# drive.net
KiCad netlist of a schematic drawn in Altium Designer
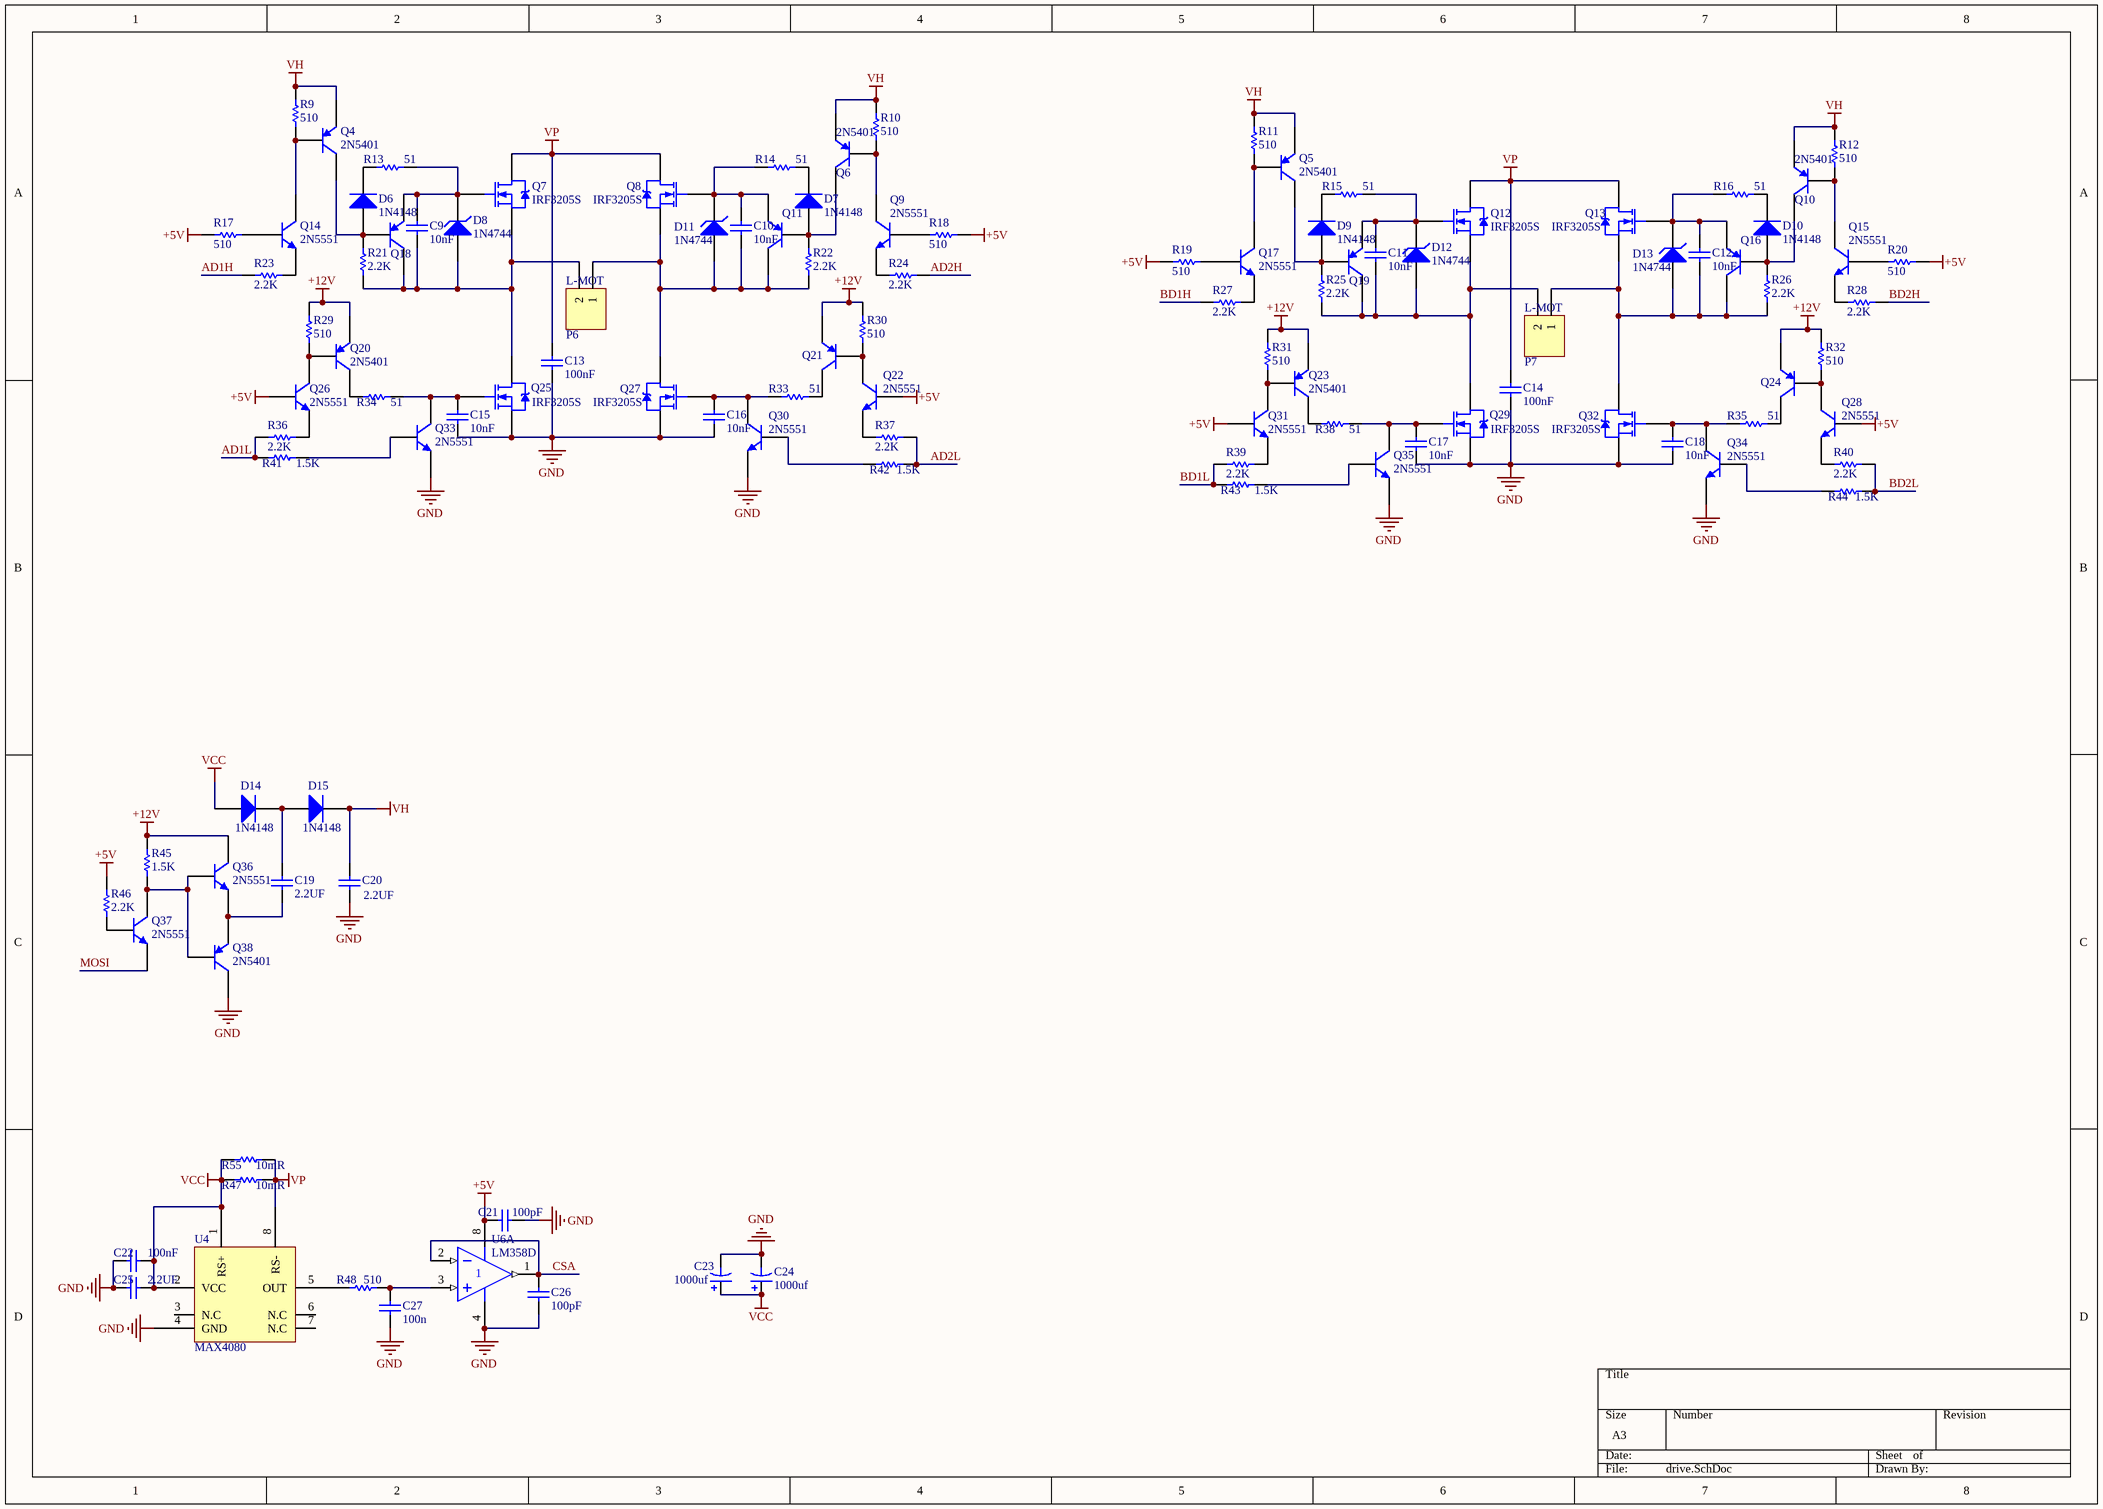
[diagram p0: drive.SchDoc]

(export (version "E")
  (design (tool "Eeschema 10.0.6"))
  (components
    (comp (ref "C9")
      (value "10nF")
      (footprint "0603")
      (description "Capacitor")
      (fields (field (name "Comment") "Cap") (field (name "PUBLISHER") "Altium Limited"))
      (libsource (lib "Miscellaneous Devices") (part "Cap"))
    )
    (comp (ref "C10")
      (value "10nF")
      (footprint "0603")
      (description "Capacitor")
      (fields (field (name "Comment") "Cap") (field (name "PUBLISHER") "Altium Limited"))
      (libsource (lib "Miscellaneous Devices") (part "Cap"))
    )
    (comp (ref "C11")
      (value "10nF")
      (footprint "0603")
      (description "Capacitor")
      (fields (field (name "Comment") "Cap") (field (name "PUBLISHER") "Altium Limited"))
      (libsource (lib "Miscellaneous Devices") (part "Cap"))
    )
    (comp (ref "C12")
      (value "10nF")
      (footprint "0603")
      (description "Capacitor")
      (fields (field (name "Comment") "Cap") (field (name "PUBLISHER") "Altium Limited"))
      (libsource (lib "Miscellaneous Devices") (part "Cap"))
    )
    (comp (ref "C13")
      (value "100nF")
      (footprint "3216[1206]")
      (description "Capacitor")
      (fields (field (name "Comment") "Cap") (field (name "PUBLISHER") "Altium Limited"))
      (libsource (lib "Miscellaneous Devices") (part "Cap"))
    )
    (comp (ref "C14")
      (value "100nF")
      (footprint "3216[1206]")
      (description "Capacitor")
      (fields (field (name "Comment") "Cap") (field (name "PUBLISHER") "Altium Limited"))
      (libsource (lib "Miscellaneous Devices") (part "Cap"))
    )
    (comp (ref "C15")
      (value "10nF")
      (footprint "0603")
      (description "Capacitor")
      (fields (field (name "Comment") "Cap") (field (name "PUBLISHER") "Altium Limited"))
      (libsource (lib "Miscellaneous Devices") (part "Cap"))
    )
    (comp (ref "C16")
      (value "10nF")
      (footprint "0603")
      (description "Capacitor")
      (fields (field (name "Comment") "Cap") (field (name "PUBLISHER") "Altium Limited"))
      (libsource (lib "Miscellaneous Devices") (part "Cap"))
    )
    (comp (ref "C17")
      (value "10nF")
      (footprint "0603")
      (description "Capacitor")
      (fields (field (name "Comment") "Cap") (field (name "PUBLISHER") "Altium Limited"))
      (libsource (lib "Miscellaneous Devices") (part "Cap"))
    )
    (comp (ref "C18")
      (value "10nF")
      (footprint "0603")
      (description "Capacitor")
      (fields (field (name "Comment") "Cap") (field (name "PUBLISHER") "Altium Limited"))
      (libsource (lib "Miscellaneous Devices") (part "Cap"))
    )
    (comp (ref "C19")
      (value "2.2UF")
      (footprint "C1206")
      (description "Capacitor")
      (fields (field (name "Comment") "Cap") (field (name "PUBLISHER") "Altium Limited"))
      (libsource (lib "Miscellaneous Devices") (part "Cap"))
    )
    (comp (ref "C20")
      (value "2.2UF")
      (footprint "C1206")
      (description "Capacitor")
      (fields (field (name "Comment") "Cap") (field (name "PUBLISHER") "Altium Limited"))
      (libsource (lib "Miscellaneous Devices") (part "Cap"))
    )
    (comp (ref "C21")
      (value "100pF")
      (footprint "0603")
      (description "Capacitor")
      (fields (field (name "Comment") "Cap") (field (name "PUBLISHER") "Altium Limited"))
      (libsource (lib "Miscellaneous Devices") (part "Cap"))
    )
    (comp (ref "C22")
      (value "100nF")
      (footprint "0603")
      (description "Capacitor")
      (fields (field (name "Comment") "Cap") (field (name "PUBLISHER") "Altium Limited"))
      (libsource (lib "Miscellaneous Devices") (part "Cap"))
    )
    (comp (ref "C23")
      (value "1000uf")
      (footprint "C16-7.5")
      (description "Polarized Capacitor (Radial)")
      (fields (field (name "Comment") "Cap Pol1") (field (name "PUBLISHER") "Altium Limited"))
      (libsource (lib "Miscellaneous Devices") (part "Cap Pol1"))
    )
    (comp (ref "C24")
      (value "1000uf")
      (footprint "C16-7.5")
      (description "Polarized Capacitor (Radial)")
      (fields (field (name "Comment") "Cap Pol1") (field (name "PUBLISHER") "Altium Limited"))
      (libsource (lib "Miscellaneous Devices") (part "Cap Pol1"))
    )
    (comp (ref "C25")
      (value "2.2UF")
      (footprint "3216[1206]")
      (description "Capacitor")
      (fields (field (name "Comment") "Cap") (field (name "PUBLISHER") "Altium Limited"))
      (libsource (lib "Miscellaneous Devices") (part "Cap"))
    )
    (comp (ref "C26")
      (value "100pF")
      (footprint "0603")
      (description "Capacitor")
      (fields (field (name "Comment") "Cap") (field (name "PUBLISHER") "Altium Limited"))
      (libsource (lib "Miscellaneous Devices") (part "Cap"))
    )
    (comp (ref "C27")
      (value "100n")
      (footprint "0603")
      (description "Capacitor")
      (fields (field (name "Comment") "Cap") (field (name "PUBLISHER") "Altium Limited"))
      (libsource (lib "Miscellaneous Devices") (part "Cap"))
    )
    (comp (ref "D6")
      (value "1N4148")
      (footprint "LL34")
      (description "High Conductance Fast Diode")
      (fields (field (name "PUBLISHER") "Altium Limited"))
      (libsource (lib "Miscellaneous Devices") (part "Diode 1N4148"))
    )
    (comp (ref "D7")
      (value "1N4148")
      (footprint "LL34")
      (description "High Conductance Fast Diode")
      (fields (field (name "PUBLISHER") "Altium Limited"))
      (libsource (lib "Miscellaneous Devices") (part "Diode 1N4148"))
    )
    (comp (ref "D8")
      (value "1N4744")
      (footprint "LL34")
      (description "Zener Diode")
      (fields (field (name "PUBLISHER") "Altium Limited"))
      (libsource (lib "Miscellaneous Devices") (part "D Zener"))
    )
    (comp (ref "D9")
      (value "1N4148")
      (footprint "LL34")
      (description "High Conductance Fast Diode")
      (fields (field (name "PUBLISHER") "Altium Limited"))
      (libsource (lib "Miscellaneous Devices") (part "Diode 1N4148"))
    )
    (comp (ref "D10")
      (value "1N4148")
      (footprint "LL34")
      (description "High Conductance Fast Diode")
      (fields (field (name "PUBLISHER") "Altium Limited"))
      (libsource (lib "Miscellaneous Devices") (part "Diode 1N4148"))
    )
    (comp (ref "D11")
      (value "1N4744")
      (footprint "LL34")
      (description "Zener Diode")
      (fields (field (name "PUBLISHER") "Altium Limited"))
      (libsource (lib "Miscellaneous Devices") (part "D Zener"))
    )
    (comp (ref "D12")
      (value "1N4744")
      (footprint "LL34")
      (description "Zener Diode")
      (fields (field (name "PUBLISHER") "Altium Limited"))
      (libsource (lib "Miscellaneous Devices") (part "D Zener"))
    )
    (comp (ref "D13")
      (value "1N4744")
      (footprint "LL34")
      (description "Zener Diode")
      (fields (field (name "PUBLISHER") "Altium Limited"))
      (libsource (lib "Miscellaneous Devices") (part "D Zener"))
    )
    (comp (ref "D14")
      (value "1N4148")
      (footprint "LL34")
      (description "3 Amp Medium Power Silicon Rectifier Diode")
      (fields (field (name "Comment") "Diode") (field (name "PUBLISHER") "Altium Limited"))
      (libsource (lib "Miscellaneous Devices") (part "Diode 1N5408"))
    )
    (comp (ref "D15")
      (value "1N4148")
      (footprint "LL34")
      (description "3 Amp Medium Power Silicon Rectifier Diode")
      (fields (field (name "Comment") "Diode") (field (name "PUBLISHER") "Altium Limited"))
      (libsource (lib "Miscellaneous Devices") (part "Diode 1N5408"))
    )
    (comp (ref "P6")
      (value "L-MOT")
      (footprint "MG7.62-2P")
      (description "Header, 2-Pin")
      (fields (field (name "PUBLISHER") "Altium Limited"))
      (libsource (lib "Miscellaneous Connectors") (part "Header 2"))
    )
    (comp (ref "P7")
      (value "L-MOT")
      (footprint "MG7.62-2P")
      (description "Header, 2-Pin")
      (fields (field (name "PUBLISHER") "Altium Limited"))
      (libsource (lib "Miscellaneous Connectors") (part "Header 2"))
    )
    (comp (ref "Q4")
      (value "2N5401")
      (footprint "SOT-23-PNP")
      (description "PNP General Purpose Amplifier")
      (fields (field (name "PUBLISHER") "Altium Limited"))
      (libsource (lib "FSC Discrete BJT") (part "2N5401"))
    )
    (comp (ref "Q5")
      (value "2N5401")
      (footprint "SOT-23-PNP")
      (description "PNP General Purpose Amplifier")
      (fields (field (name "PUBLISHER") "Altium Limited"))
      (libsource (lib "FSC Discrete BJT") (part "2N5401"))
    )
    (comp (ref "Q6")
      (value "2N5401")
      (footprint "SOT-23-PNP")
      (description "PNP General Purpose Amplifier")
      (fields (field (name "PUBLISHER") "Altium Limited"))
      (libsource (lib "FSC Discrete BJT") (part "2N5401"))
    )
    (comp (ref "Q7")
      (value "IRF3205S")
      (footprint "D2PAK-263")
      (description "HEXFET Power MOSFET")
      (fields (field (name "PUBLISHER") "Altium Limited"))
      (libsource (lib "Tank") (part "IRF3205S"))
    )
    (comp (ref "Q8")
      (value "IRF3205S")
      (footprint "D2PAK-263")
      (description "HEXFET Power MOSFET")
      (fields (field (name "PUBLISHER") "Altium Limited"))
      (libsource (lib "IR Discrete MOSFET - Power") (part "IRF3205S"))
    )
    (comp (ref "Q9")
      (value "2N5551")
      (footprint "SOT-23-NPN")
      (description "NPN General Purpose Amplifier")
      (fields (field (name "PUBLISHER") "Altium Limited"))
      (libsource (lib "FSC Discrete BJT") (part "2N5551"))
    )
    (comp (ref "Q10")
      (value "2N5401")
      (footprint "SOT-23-PNP")
      (description "PNP General Purpose Amplifier")
      (fields (field (name "PUBLISHER") "Altium Limited"))
      (libsource (lib "FSC Discrete BJT") (part "2N5401"))
    )
    (comp (ref "Q11")
      (value "2N5401")
      (footprint "SOT-23-PNP")
      (description "PNP General Purpose Amplifier")
      (fields (field (name "PUBLISHER") "Altium Limited"))
      (libsource (lib "FSC Discrete BJT") (part "2N5401"))
    )
    (comp (ref "Q12")
      (value "IRF3205S")
      (footprint "D2PAK-263")
      (description "HEXFET Power MOSFET")
      (fields (field (name "PUBLISHER") "Altium Limited"))
      (libsource (lib "Tank") (part "IRF3205S"))
    )
    (comp (ref "Q13")
      (value "IRF3205S")
      (footprint "D2PAK-263")
      (description "HEXFET Power MOSFET")
      (fields (field (name "PUBLISHER") "Altium Limited"))
      (libsource (lib "IR Discrete MOSFET - Power") (part "IRF3205S"))
    )
    (comp (ref "Q14")
      (value "2N5551")
      (footprint "SOT-23-NPN")
      (description "NPN General Purpose Amplifier")
      (fields (field (name "PUBLISHER") "Altium Limited"))
      (libsource (lib "FSC Discrete BJT") (part "2N5551"))
    )
    (comp (ref "Q15")
      (value "2N5551")
      (footprint "SOT-23-NPN")
      (description "NPN General Purpose Amplifier")
      (fields (field (name "PUBLISHER") "Altium Limited"))
      (libsource (lib "FSC Discrete BJT") (part "2N5551"))
    )
    (comp (ref "Q16")
      (value "2N5401")
      (footprint "SOT-23-PNP")
      (description "PNP General Purpose Amplifier")
      (fields (field (name "PUBLISHER") "Altium Limited"))
      (libsource (lib "FSC Discrete BJT") (part "2N5401"))
    )
    (comp (ref "Q17")
      (value "2N5551")
      (footprint "SOT-23-NPN")
      (description "NPN General Purpose Amplifier")
      (fields (field (name "PUBLISHER") "Altium Limited"))
      (libsource (lib "FSC Discrete BJT") (part "2N5551"))
    )
    (comp (ref "Q18")
      (value "2N5401")
      (footprint "SOT-23-PNP")
      (description "PNP General Purpose Amplifier")
      (fields (field (name "PUBLISHER") "Altium Limited"))
      (libsource (lib "FSC Discrete BJT") (part "2N5401"))
    )
    (comp (ref "Q19")
      (value "2N5401")
      (footprint "SOT-23-PNP")
      (description "PNP General Purpose Amplifier")
      (fields (field (name "PUBLISHER") "Altium Limited"))
      (libsource (lib "FSC Discrete BJT") (part "2N5401"))
    )
    (comp (ref "Q20")
      (value "2N5401")
      (footprint "SOT-23-PNP")
      (description "PNP General Purpose Amplifier")
      (fields (field (name "PUBLISHER") "Altium Limited"))
      (libsource (lib "FSC Discrete BJT") (part "2N5401"))
    )
    (comp (ref "Q21")
      (value "2N5401")
      (footprint "SOT-23-PNP")
      (description "PNP General Purpose Amplifier")
      (fields (field (name "PUBLISHER") "Altium Limited"))
      (libsource (lib "FSC Discrete BJT") (part "2N5401"))
    )
    (comp (ref "Q22")
      (value "2N5551")
      (footprint "SOT-23-NPN")
      (description "NPN General Purpose Amplifier")
      (fields (field (name "PUBLISHER") "Altium Limited"))
      (libsource (lib "FSC Discrete BJT") (part "2N5551"))
    )
    (comp (ref "Q23")
      (value "2N5401")
      (footprint "SOT-23-PNP")
      (description "PNP General Purpose Amplifier")
      (fields (field (name "PUBLISHER") "Altium Limited"))
      (libsource (lib "FSC Discrete BJT") (part "2N5401"))
    )
    (comp (ref "Q24")
      (value "2N5401")
      (footprint "SOT-23-PNP")
      (description "PNP General Purpose Amplifier")
      (fields (field (name "PUBLISHER") "Altium Limited"))
      (libsource (lib "FSC Discrete BJT") (part "2N5401"))
    )
    (comp (ref "Q25")
      (value "IRF3205S")
      (footprint "D2PAK-263")
      (description "HEXFET Power MOSFET")
      (fields (field (name "PUBLISHER") "Altium Limited"))
      (libsource (lib "IR Discrete MOSFET - Power") (part "IRF3205S"))
    )
    (comp (ref "Q26")
      (value "2N5551")
      (footprint "SOT-23-NPN")
      (description "NPN General Purpose Amplifier")
      (fields (field (name "PUBLISHER") "Altium Limited"))
      (libsource (lib "FSC Discrete BJT") (part "2N5551"))
    )
    (comp (ref "Q27")
      (value "IRF3205S")
      (footprint "D2PAK-263")
      (description "HEXFET Power MOSFET")
      (fields (field (name "PUBLISHER") "Altium Limited"))
      (libsource (lib "IR Discrete MOSFET - Power") (part "IRF3205S"))
    )
    (comp (ref "Q28")
      (value "2N5551")
      (footprint "SOT-23-NPN")
      (description "NPN General Purpose Amplifier")
      (fields (field (name "PUBLISHER") "Altium Limited"))
      (libsource (lib "FSC Discrete BJT") (part "2N5551"))
    )
    (comp (ref "Q29")
      (value "IRF3205S")
      (footprint "D2PAK-263")
      (description "HEXFET Power MOSFET")
      (fields (field (name "PUBLISHER") "Altium Limited"))
      (libsource (lib "IR Discrete MOSFET - Power") (part "IRF3205S"))
    )
    (comp (ref "Q30")
      (value "2N5551")
      (footprint "SOT-23-NPN")
      (description "NPN General Purpose Amplifier")
      (fields (field (name "PUBLISHER") "Altium Limited"))
      (libsource (lib "FSC Discrete BJT") (part "2N5551"))
    )
    (comp (ref "Q31")
      (value "2N5551")
      (footprint "SOT-23-NPN")
      (description "NPN General Purpose Amplifier")
      (fields (field (name "PUBLISHER") "Altium Limited"))
      (libsource (lib "FSC Discrete BJT") (part "2N5551"))
    )
    (comp (ref "Q32")
      (value "IRF3205S")
      (footprint "D2PAK-263")
      (description "HEXFET Power MOSFET")
      (fields (field (name "PUBLISHER") "Altium Limited"))
      (libsource (lib "IR Discrete MOSFET - Power") (part "IRF3205S"))
    )
    (comp (ref "Q33")
      (value "2N5551")
      (footprint "SOT-23-NPN")
      (description "NPN General Purpose Amplifier")
      (fields (field (name "PUBLISHER") "Altium Limited"))
      (libsource (lib "FSC Discrete BJT") (part "2N5551"))
    )
    (comp (ref "Q34")
      (value "2N5551")
      (footprint "SOT-23-NPN")
      (description "NPN General Purpose Amplifier")
      (fields (field (name "PUBLISHER") "Altium Limited"))
      (libsource (lib "FSC Discrete BJT") (part "2N5551"))
    )
    (comp (ref "Q35")
      (value "2N5551")
      (footprint "SOT-23-NPN")
      (description "NPN General Purpose Amplifier")
      (fields (field (name "PUBLISHER") "Altium Limited"))
      (libsource (lib "FSC Discrete BJT") (part "2N5551"))
    )
    (comp (ref "Q36")
      (value "2N5551")
      (footprint "SOT-23-NPN")
      (description "NPN General Purpose Amplifier")
      (fields (field (name "Comment") "NPN") (field (name "PUBLISHER") "Altium Limited"))
      (libsource (lib "FSC Discrete BJT") (part "2N5551"))
    )
    (comp (ref "Q37")
      (value "2N5551")
      (footprint "SOT-23-NPN")
      (description "NPN General Purpose Amplifier")
      (fields (field (name "Comment") "NPN") (field (name "PUBLISHER") "Altium Limited"))
      (libsource (lib "FSC Discrete BJT") (part "2N5551"))
    )
    (comp (ref "Q38")
      (value "2N5401")
      (footprint "SOT-23-PNP")
      (description "PNP General Purpose Amplifier")
      (fields (field (name "Comment") "PNP") (field (name "PUBLISHER") "Altium Limited"))
      (libsource (lib "FSC Discrete BJT") (part "2N5401"))
    )
    (comp (ref "R9")
      (value "510")
      (footprint "0603")
      (description "Resistor")
      (fields (field (name "Comment") "Res1") (field (name "PUBLISHER") "Altium Limited"))
      (libsource (lib "Miscellaneous Devices") (part "Res1"))
    )
    (comp (ref "R10")
      (value "510")
      (footprint "0603")
      (description "Resistor")
      (fields (field (name "Comment") "Res1") (field (name "PUBLISHER") "Altium Limited"))
      (libsource (lib "Miscellaneous Devices") (part "Res1"))
    )
    (comp (ref "R11")
      (value "510")
      (footprint "0603")
      (description "Resistor")
      (fields (field (name "Comment") "Res1") (field (name "PUBLISHER") "Altium Limited"))
      (libsource (lib "Miscellaneous Devices") (part "Res1"))
    )
    (comp (ref "R12")
      (value "510")
      (footprint "0603")
      (description "Resistor")
      (fields (field (name "Comment") "Res1") (field (name "PUBLISHER") "Altium Limited"))
      (libsource (lib "Miscellaneous Devices") (part "Res1"))
    )
    (comp (ref "R13")
      (value "51")
      (footprint "0603")
      (description "Resistor")
      (fields (field (name "Comment") "Res1") (field (name "PUBLISHER") "Altium Limited"))
      (libsource (lib "Miscellaneous Devices") (part "Res1"))
    )
    (comp (ref "R14")
      (value "51")
      (footprint "0603")
      (description "Resistor")
      (fields (field (name "Comment") "Res1") (field (name "PUBLISHER") "Altium Limited"))
      (libsource (lib "Miscellaneous Devices") (part "Res1"))
    )
    (comp (ref "R15")
      (value "51")
      (footprint "0603")
      (description "Resistor")
      (fields (field (name "Comment") "Res1") (field (name "PUBLISHER") "Altium Limited"))
      (libsource (lib "Miscellaneous Devices") (part "Res1"))
    )
    (comp (ref "R16")
      (value "51")
      (footprint "0603")
      (description "Resistor")
      (fields (field (name "Comment") "Res1") (field (name "PUBLISHER") "Altium Limited"))
      (libsource (lib "Miscellaneous Devices") (part "Res1"))
    )
    (comp (ref "R17")
      (value "510")
      (footprint "0603")
      (description "Resistor")
      (fields (field (name "Comment") "Res1") (field (name "PUBLISHER") "Altium Limited"))
      (libsource (lib "Miscellaneous Devices") (part "Res1"))
    )
    (comp (ref "R18")
      (value "510")
      (footprint "0603")
      (description "Resistor")
      (fields (field (name "Comment") "Res1") (field (name "PUBLISHER") "Altium Limited"))
      (libsource (lib "Miscellaneous Devices") (part "Res1"))
    )
    (comp (ref "R19")
      (value "510")
      (footprint "0603")
      (description "Resistor")
      (fields (field (name "Comment") "Res1") (field (name "PUBLISHER") "Altium Limited"))
      (libsource (lib "Miscellaneous Devices") (part "Res1"))
    )
    (comp (ref "R20")
      (value "510")
      (footprint "0603")
      (description "Resistor")
      (fields (field (name "Comment") "Res1") (field (name "PUBLISHER") "Altium Limited"))
      (libsource (lib "Miscellaneous Devices") (part "Res1"))
    )
    (comp (ref "R21")
      (value "2.2K")
      (footprint "0603")
      (description "Resistor")
      (fields (field (name "Comment") "Res1") (field (name "PUBLISHER") "Altium Limited"))
      (libsource (lib "Miscellaneous Devices") (part "Res1"))
    )
    (comp (ref "R22")
      (value "2.2K")
      (footprint "0603")
      (description "Resistor")
      (fields (field (name "Comment") "Res1") (field (name "PUBLISHER") "Altium Limited"))
      (libsource (lib "Miscellaneous Devices") (part "Res1"))
    )
    (comp (ref "R23")
      (value "2.2K")
      (footprint "0603")
      (description "Resistor")
      (fields (field (name "Comment") "Res1") (field (name "PUBLISHER") "Altium Limited"))
      (libsource (lib "Miscellaneous Devices") (part "Res1"))
    )
    (comp (ref "R24")
      (value "2.2K")
      (footprint "0603")
      (description "Resistor")
      (fields (field (name "Comment") "Res1") (field (name "PUBLISHER") "Altium Limited"))
      (libsource (lib "Miscellaneous Devices") (part "Res1"))
    )
    (comp (ref "R25")
      (value "2.2K")
      (footprint "0603")
      (description "Resistor")
      (fields (field (name "Comment") "Res1") (field (name "PUBLISHER") "Altium Limited"))
      (libsource (lib "Miscellaneous Devices") (part "Res1"))
    )
    (comp (ref "R26")
      (value "2.2K")
      (footprint "0603")
      (description "Resistor")
      (fields (field (name "Comment") "Res1") (field (name "PUBLISHER") "Altium Limited"))
      (libsource (lib "Miscellaneous Devices") (part "Res1"))
    )
    (comp (ref "R27")
      (value "2.2K")
      (footprint "0603")
      (description "Resistor")
      (fields (field (name "Comment") "Res1") (field (name "PUBLISHER") "Altium Limited"))
      (libsource (lib "Miscellaneous Devices") (part "Res1"))
    )
    (comp (ref "R28")
      (value "2.2K")
      (footprint "0603")
      (description "Resistor")
      (fields (field (name "Comment") "Res1") (field (name "PUBLISHER") "Altium Limited"))
      (libsource (lib "Miscellaneous Devices") (part "Res1"))
    )
    (comp (ref "R29")
      (value "510")
      (footprint "0603")
      (description "Resistor")
      (fields (field (name "Comment") "Res1") (field (name "PUBLISHER") "Altium Limited"))
      (libsource (lib "Miscellaneous Devices") (part "Res1"))
    )
    (comp (ref "R30")
      (value "510")
      (footprint "0603")
      (description "Resistor")
      (fields (field (name "Comment") "Res1") (field (name "PUBLISHER") "Altium Limited"))
      (libsource (lib "Miscellaneous Devices") (part "Res1"))
    )
    (comp (ref "R31")
      (value "510")
      (footprint "0603")
      (description "Resistor")
      (fields (field (name "Comment") "Res1") (field (name "PUBLISHER") "Altium Limited"))
      (libsource (lib "Miscellaneous Devices") (part "Res1"))
    )
    (comp (ref "R32")
      (value "510")
      (footprint "0603")
      (description "Resistor")
      (fields (field (name "Comment") "Res1") (field (name "PUBLISHER") "Altium Limited"))
      (libsource (lib "Miscellaneous Devices") (part "Res1"))
    )
    (comp (ref "R33")
      (value "51")
      (footprint "0603")
      (description "Resistor")
      (fields (field (name "Comment") "Res1") (field (name "PUBLISHER") "Altium Limited"))
      (libsource (lib "Miscellaneous Devices") (part "Res1"))
    )
    (comp (ref "R34")
      (value "51")
      (footprint "0603")
      (description "Resistor")
      (fields (field (name "Comment") "Res1") (field (name "PUBLISHER") "Altium Limited"))
      (libsource (lib "Miscellaneous Devices") (part "Res1"))
    )
    (comp (ref "R35")
      (value "51")
      (footprint "0603")
      (description "Resistor")
      (fields (field (name "Comment") "Res1") (field (name "PUBLISHER") "Altium Limited"))
      (libsource (lib "Miscellaneous Devices") (part "Res1"))
    )
    (comp (ref "R36")
      (value "2.2K")
      (footprint "0603")
      (description "Resistor")
      (fields (field (name "Comment") "Res1") (field (name "PUBLISHER") "Altium Limited"))
      (libsource (lib "Miscellaneous Devices") (part "Res1"))
    )
    (comp (ref "R37")
      (value "2.2K")
      (footprint "0603")
      (description "Resistor")
      (fields (field (name "Comment") "Res1") (field (name "PUBLISHER") "Altium Limited"))
      (libsource (lib "Miscellaneous Devices") (part "Res1"))
    )
    (comp (ref "R38")
      (value "51")
      (footprint "0603")
      (description "Resistor")
      (fields (field (name "Comment") "Res1") (field (name "PUBLISHER") "Altium Limited"))
      (libsource (lib "Miscellaneous Devices") (part "Res1"))
    )
    (comp (ref "R39")
      (value "2.2K")
      (footprint "0603")
      (description "Resistor")
      (fields (field (name "Comment") "Res1") (field (name "PUBLISHER") "Altium Limited"))
      (libsource (lib "Miscellaneous Devices") (part "Res1"))
    )
    (comp (ref "R40")
      (value "2.2K")
      (footprint "0603")
      (description "Resistor")
      (fields (field (name "Comment") "Res1") (field (name "PUBLISHER") "Altium Limited"))
      (libsource (lib "Miscellaneous Devices") (part "Res1"))
    )
    (comp (ref "R41")
      (value "1.5K")
      (footprint "0603")
      (description "Resistor")
      (fields (field (name "Comment") "Res1") (field (name "PUBLISHER") "Altium Limited"))
      (libsource (lib "Miscellaneous Devices") (part "Res1"))
    )
    (comp (ref "R42")
      (value "1.5K")
      (footprint "0603")
      (description "Resistor")
      (fields (field (name "Comment") "Res1") (field (name "PUBLISHER") "Altium Limited"))
      (libsource (lib "Miscellaneous Devices") (part "Res1"))
    )
    (comp (ref "R43")
      (value "1.5K")
      (footprint "0603")
      (description "Resistor")
      (fields (field (name "Comment") "Res1") (field (name "PUBLISHER") "Altium Limited"))
      (libsource (lib "Miscellaneous Devices") (part "Res1"))
    )
    (comp (ref "R44")
      (value "1.5K")
      (footprint "0603")
      (description "Resistor")
      (fields (field (name "Comment") "Res1") (field (name "PUBLISHER") "Altium Limited"))
      (libsource (lib "Miscellaneous Devices") (part "Res1"))
    )
    (comp (ref "R45")
      (value "1.5K")
      (footprint "0603")
      (description "Resistor")
      (fields (field (name "Comment") "Res1") (field (name "PUBLISHER") "Altium Limited"))
      (libsource (lib "Miscellaneous Devices") (part "Res1"))
    )
    (comp (ref "R46")
      (value "2.2K")
      (footprint "0603")
      (description "Resistor")
      (fields (field (name "Comment") "Res1") (field (name "PUBLISHER") "Altium Limited"))
      (libsource (lib "Miscellaneous Devices") (part "Res1"))
    )
    (comp (ref "R47")
      (value "10mR")
      (footprint "R15-1mm")
      (description "Resistor")
      (fields (field (name "PUBLISHER") "Altium Limited"))
      (libsource (lib "Miscellaneous Devices") (part "Res1"))
    )
    (comp (ref "R48")
      (value "510")
      (footprint "0603")
      (description "Resistor")
      (fields (field (name "Comment") "Res1") (field (name "PUBLISHER") "Altium Limited"))
      (libsource (lib "Miscellaneous Devices") (part "Res1"))
    )
    (comp (ref "R55")
      (value "10mR")
      (footprint "R15-1mm")
      (description "Resistor")
      (fields (field (name "PUBLISHER") "Altium Limited"))
      (libsource (lib "Miscellaneous Devices") (part "Res1"))
    )
    (comp (ref "U4") (value "MAX4080") (footprint "SOIC8") (libsource (lib "Tank") (part "MAX4080")))
    (comp (ref "U6")
      (value "LM358D")
      (footprint "SOIC8")
      (description "Dual Low-Power Operational Amplifier")
      (fields (field (name "PUBLISHER") "Altium Limited"))
      (libsource (lib "Motorola Amplifier Operational Amplifier") (part "LM358D"))
    )
  )
  (nets
    (net (code "1") (name "+5V") (class "Default")
      (node (ref "C21") (pin "2") (pinfunction "2_2") (pintype "passive"))
      (node (ref "Q22") (pin "2") (pinfunction "B_2") (pintype "passive"))
      (node (ref "Q26") (pin "2") (pinfunction "B_2") (pintype "passive"))
      (node (ref "Q28") (pin "2") (pinfunction "B_2") (pintype "passive"))
      (node (ref "Q31") (pin "2") (pinfunction "B_2") (pintype "passive"))
      (node (ref "R17") (pin "2") (pinfunction "2_2") (pintype "passive"))
      (node (ref "R18") (pin "2") (pinfunction "2_2") (pintype "passive"))
      (node (ref "R19") (pin "2") (pinfunction "2_2") (pintype "passive"))
      (node (ref "R20") (pin "2") (pinfunction "2_2") (pintype "passive"))
      (node (ref "R46") (pin "2") (pinfunction "2_2") (pintype "passive"))
      (node (ref "U6") (pin "8") (pinfunction "V+_8") (pintype "power_in"))
    )
    (net (code "2") (name "+12V") (class "Default")
      (node (ref "Q20") (pin "1") (pinfunction "E_1") (pintype "passive"))
      (node (ref "Q21") (pin "1") (pinfunction "E_1") (pintype "passive"))
      (node (ref "Q23") (pin "1") (pinfunction "E_1") (pintype "passive"))
      (node (ref "Q24") (pin "1") (pinfunction "E_1") (pintype "passive"))
      (node (ref "Q36") (pin "3") (pinfunction "C_3") (pintype "passive"))
      (node (ref "R29") (pin "1") (pinfunction "1_1") (pintype "passive"))
      (node (ref "R30") (pin "1") (pinfunction "1_1") (pintype "passive"))
      (node (ref "R31") (pin "1") (pinfunction "1_1") (pintype "passive"))
      (node (ref "R32") (pin "1") (pinfunction "1_1") (pintype "passive"))
      (node (ref "R45") (pin "2") (pinfunction "2_2") (pintype "passive"))
    )
    (net (code "3") (name "/AD1H") (class "Default")
      (node (ref "R23") (pin "1") (pinfunction "1_1") (pintype "passive"))
    )
    (net (code "4") (name "/AD1L") (class "Default")
      (node (ref "R36") (pin "1") (pinfunction "1_1") (pintype "passive"))
      (node (ref "R41") (pin "2") (pinfunction "2_2") (pintype "passive"))
    )
    (net (code "5") (name "/AD2H") (class "Default")
      (node (ref "R24") (pin "2") (pinfunction "2_2") (pintype "passive"))
    )
    (net (code "6") (name "/AD2L") (class "Default")
      (node (ref "R37") (pin "2") (pinfunction "2_2") (pintype "passive"))
      (node (ref "R42") (pin "1") (pinfunction "1_1") (pintype "passive"))
    )
    (net (code "7") (name "/BD1H") (class "Default")
      (node (ref "R27") (pin "1") (pinfunction "1_1") (pintype "passive"))
    )
    (net (code "8") (name "/BD1L") (class "Default")
      (node (ref "R39") (pin "1") (pinfunction "1_1") (pintype "passive"))
      (node (ref "R43") (pin "2") (pinfunction "2_2") (pintype "passive"))
    )
    (net (code "9") (name "/BD2H") (class "Default")
      (node (ref "R28") (pin "2") (pinfunction "2_2") (pintype "passive"))
    )
    (net (code "10") (name "/BD2L") (class "Default")
      (node (ref "R40") (pin "2") (pinfunction "2_2") (pintype "passive"))
      (node (ref "R44") (pin "1") (pinfunction "1_1") (pintype "passive"))
    )
    (net (code "11") (name "/CSA") (class "Default")
      (node (ref "C26") (pin "2") (pinfunction "2_2") (pintype "passive"))
      (node (ref "U6") (pin "1") (pinfunction "OUT_1") (pintype "output"))
      (node (ref "U6") (pin "2") (pinfunction "IN-_2") (pintype "input"))
    )
    (net (code "12") (name "/MOSI") (class "Default")
      (node (ref "Q37") (pin "1") (pinfunction "E_1") (pintype "passive"))
    )
    (net (code "13") (name "GND") (class "Default")
      (node (ref "C13") (pin "2") (pinfunction "2_2") (pintype "passive"))
      (node (ref "C14") (pin "2") (pinfunction "2_2") (pintype "passive"))
      (node (ref "C15") (pin "2") (pinfunction "2_2") (pintype "passive"))
      (node (ref "C16") (pin "2") (pinfunction "2_2") (pintype "passive"))
      (node (ref "C17") (pin "2") (pinfunction "2_2") (pintype "passive"))
      (node (ref "C18") (pin "2") (pinfunction "2_2") (pintype "passive"))
      (node (ref "C20") (pin "1") (pinfunction "1_1") (pintype "passive"))
      (node (ref "C21") (pin "1") (pinfunction "1_1") (pintype "passive"))
      (node (ref "C22") (pin "1") (pinfunction "1_1") (pintype "passive"))
      (node (ref "C23") (pin "2") (pinfunction "2_2") (pintype "passive"))
      (node (ref "C24") (pin "2") (pinfunction "2_2") (pintype "passive"))
      (node (ref "C25") (pin "2") (pinfunction "2_2") (pintype "passive"))
      (node (ref "C26") (pin "1") (pinfunction "1_1") (pintype "passive"))
      (node (ref "C27") (pin "1") (pinfunction "1_1") (pintype "passive"))
      (node (ref "Q25") (pin "3") (pinfunction "S_3") (pintype "passive"))
      (node (ref "Q27") (pin "3") (pinfunction "S_3") (pintype "passive"))
      (node (ref "Q29") (pin "3") (pinfunction "S_3") (pintype "passive"))
      (node (ref "Q30") (pin "1") (pinfunction "E_1") (pintype "passive"))
      (node (ref "Q32") (pin "3") (pinfunction "S_3") (pintype "passive"))
      (node (ref "Q33") (pin "1") (pinfunction "E_1") (pintype "passive"))
      (node (ref "Q34") (pin "1") (pinfunction "E_1") (pintype "passive"))
      (node (ref "Q35") (pin "1") (pinfunction "E_1") (pintype "passive"))
      (node (ref "Q38") (pin "3") (pinfunction "C_3") (pintype "passive"))
      (node (ref "U4") (pin "4") (pinfunction "GND_4") (pintype "passive"))
      (node (ref "U6") (pin "4") (pinfunction "V-_4") (pintype "power_in"))
    )
    (net (code "14") (name "Net-(D6-A)") (class "Default")
      (node (ref "D6") (pin "1") (pinfunction "A_1") (pintype "passive"))
      (node (ref "Q18") (pin "2") (pinfunction "B_2") (pintype "passive"))
      (node (ref "Q4") (pin "3") (pinfunction "C_3") (pintype "passive"))
      (node (ref "R21") (pin "2") (pinfunction "2_2") (pintype "passive"))
    )
    (net (code "15") (name "Net-(D6-K)") (class "Default")
      (node (ref "D6") (pin "2") (pinfunction "K_2") (pintype "passive"))
      (node (ref "R13") (pin "1") (pinfunction "1_1") (pintype "passive"))
    )
    (net (code "16") (name "Net-(D7-A)") (class "Default")
      (node (ref "D7") (pin "1") (pinfunction "A_1") (pintype "passive"))
      (node (ref "Q11") (pin "2") (pinfunction "B_2") (pintype "passive"))
      (node (ref "Q6") (pin "3") (pinfunction "C_3") (pintype "passive"))
      (node (ref "R22") (pin "2") (pinfunction "2_2") (pintype "passive"))
    )
    (net (code "17") (name "Net-(D7-K)") (class "Default")
      (node (ref "D7") (pin "2") (pinfunction "K_2") (pintype "passive"))
      (node (ref "R14") (pin "2") (pinfunction "2_2") (pintype "passive"))
    )
    (net (code "18") (name "Net-(D8-A)") (class "Default")
      (node (ref "C9") (pin "2") (pinfunction "2_2") (pintype "passive"))
      (node (ref "D8") (pin "1") (pinfunction "A_1") (pintype "passive"))
      (node (ref "P6") (pin "2") (pinfunction "2_2") (pintype "passive"))
      (node (ref "Q18") (pin "3") (pinfunction "C_3") (pintype "passive"))
      (node (ref "Q25") (pin "2") (pinfunction "D_2") (pintype "passive"))
      (node (ref "Q7") (pin "3") (pinfunction "S_3") (pintype "passive"))
      (node (ref "R21") (pin "1") (pinfunction "1_1") (pintype "passive"))
    )
    (net (code "19") (name "Net-(D8-K)") (class "Default")
      (node (ref "C9") (pin "1") (pinfunction "1_1") (pintype "passive"))
      (node (ref "D8") (pin "2") (pinfunction "K_2") (pintype "passive"))
      (node (ref "Q18") (pin "1") (pinfunction "E_1") (pintype "passive"))
      (node (ref "Q7") (pin "1") (pinfunction "G_1") (pintype "passive"))
      (node (ref "R13") (pin "2") (pinfunction "2_2") (pintype "passive"))
    )
    (net (code "20") (name "Net-(D9-A)") (class "Default")
      (node (ref "D9") (pin "1") (pinfunction "A_1") (pintype "passive"))
      (node (ref "Q19") (pin "2") (pinfunction "B_2") (pintype "passive"))
      (node (ref "Q5") (pin "3") (pinfunction "C_3") (pintype "passive"))
      (node (ref "R25") (pin "2") (pinfunction "2_2") (pintype "passive"))
    )
    (net (code "21") (name "Net-(D9-K)") (class "Default")
      (node (ref "D9") (pin "2") (pinfunction "K_2") (pintype "passive"))
      (node (ref "R15") (pin "1") (pinfunction "1_1") (pintype "passive"))
    )
    (net (code "22") (name "Net-(D10-A)") (class "Default")
      (node (ref "D10") (pin "1") (pinfunction "A_1") (pintype "passive"))
      (node (ref "Q10") (pin "3") (pinfunction "C_3") (pintype "passive"))
      (node (ref "Q16") (pin "2") (pinfunction "B_2") (pintype "passive"))
      (node (ref "R26") (pin "2") (pinfunction "2_2") (pintype "passive"))
    )
    (net (code "23") (name "Net-(D10-K)") (class "Default")
      (node (ref "D10") (pin "2") (pinfunction "K_2") (pintype "passive"))
      (node (ref "R16") (pin "2") (pinfunction "2_2") (pintype "passive"))
    )
    (net (code "24") (name "Net-(D11-A)") (class "Default")
      (node (ref "C10") (pin "2") (pinfunction "2_2") (pintype "passive"))
      (node (ref "D11") (pin "1") (pinfunction "A_1") (pintype "passive"))
      (node (ref "P6") (pin "1") (pinfunction "1_1") (pintype "passive"))
      (node (ref "Q11") (pin "3") (pinfunction "C_3") (pintype "passive"))
      (node (ref "Q27") (pin "2") (pinfunction "D_2") (pintype "passive"))
      (node (ref "Q8") (pin "3") (pinfunction "S_3") (pintype "passive"))
      (node (ref "R22") (pin "1") (pinfunction "1_1") (pintype "passive"))
    )
    (net (code "25") (name "Net-(D11-K)") (class "Default")
      (node (ref "C10") (pin "1") (pinfunction "1_1") (pintype "passive"))
      (node (ref "D11") (pin "2") (pinfunction "K_2") (pintype "passive"))
      (node (ref "Q11") (pin "1") (pinfunction "E_1") (pintype "passive"))
      (node (ref "Q8") (pin "1") (pinfunction "G_1") (pintype "passive"))
      (node (ref "R14") (pin "1") (pinfunction "1_1") (pintype "passive"))
    )
    (net (code "26") (name "Net-(D12-A)") (class "Default")
      (node (ref "C11") (pin "2") (pinfunction "2_2") (pintype "passive"))
      (node (ref "D12") (pin "1") (pinfunction "A_1") (pintype "passive"))
      (node (ref "P7") (pin "2") (pinfunction "2_2") (pintype "passive"))
      (node (ref "Q12") (pin "3") (pinfunction "S_3") (pintype "passive"))
      (node (ref "Q19") (pin "3") (pinfunction "C_3") (pintype "passive"))
      (node (ref "Q29") (pin "2") (pinfunction "D_2") (pintype "passive"))
      (node (ref "R25") (pin "1") (pinfunction "1_1") (pintype "passive"))
    )
    (net (code "27") (name "Net-(D12-K)") (class "Default")
      (node (ref "C11") (pin "1") (pinfunction "1_1") (pintype "passive"))
      (node (ref "D12") (pin "2") (pinfunction "K_2") (pintype "passive"))
      (node (ref "Q12") (pin "1") (pinfunction "G_1") (pintype "passive"))
      (node (ref "Q19") (pin "1") (pinfunction "E_1") (pintype "passive"))
      (node (ref "R15") (pin "2") (pinfunction "2_2") (pintype "passive"))
    )
    (net (code "28") (name "Net-(D13-A)") (class "Default")
      (node (ref "C12") (pin "2") (pinfunction "2_2") (pintype "passive"))
      (node (ref "D13") (pin "1") (pinfunction "A_1") (pintype "passive"))
      (node (ref "P7") (pin "1") (pinfunction "1_1") (pintype "passive"))
      (node (ref "Q13") (pin "3") (pinfunction "S_3") (pintype "passive"))
      (node (ref "Q16") (pin "3") (pinfunction "C_3") (pintype "passive"))
      (node (ref "Q32") (pin "2") (pinfunction "D_2") (pintype "passive"))
      (node (ref "R26") (pin "1") (pinfunction "1_1") (pintype "passive"))
    )
    (net (code "29") (name "Net-(D13-K)") (class "Default")
      (node (ref "C12") (pin "1") (pinfunction "1_1") (pintype "passive"))
      (node (ref "D13") (pin "2") (pinfunction "K_2") (pintype "passive"))
      (node (ref "Q13") (pin "1") (pinfunction "G_1") (pintype "passive"))
      (node (ref "Q16") (pin "1") (pinfunction "E_1") (pintype "passive"))
      (node (ref "R16") (pin "1") (pinfunction "1_1") (pintype "passive"))
    )
    (net (code "30") (name "Net-(D14-K)") (class "Default")
      (node (ref "C19") (pin "1") (pinfunction "1_1") (pintype "passive"))
      (node (ref "D14") (pin "2") (pinfunction "K_2") (pintype "passive"))
      (node (ref "D15") (pin "1") (pinfunction "A_1") (pintype "passive"))
    )
    (net (code "31") (name "Net-(Q6-B)") (class "Default")
      (node (ref "Q6") (pin "2") (pinfunction "B_2") (pintype "passive"))
      (node (ref "Q9") (pin "3") (pinfunction "C_3") (pintype "passive"))
      (node (ref "R10") (pin "2") (pinfunction "2_2") (pintype "passive"))
    )
    (net (code "32") (name "Net-(Q9-B)") (class "Default")
      (node (ref "Q9") (pin "2") (pinfunction "B_2") (pintype "passive"))
      (node (ref "R18") (pin "1") (pinfunction "1_1") (pintype "passive"))
    )
    (net (code "33") (name "Net-(Q9-E)") (class "Default")
      (node (ref "Q9") (pin "1") (pinfunction "E_1") (pintype "passive"))
      (node (ref "R24") (pin "1") (pinfunction "1_1") (pintype "passive"))
    )
    (net (code "34") (name "Net-(Q10-B)") (class "Default")
      (node (ref "Q10") (pin "2") (pinfunction "B_2") (pintype "passive"))
      (node (ref "Q15") (pin "3") (pinfunction "C_3") (pintype "passive"))
      (node (ref "R12") (pin "2") (pinfunction "2_2") (pintype "passive"))
    )
    (net (code "35") (name "Net-(Q14-B)") (class "Default")
      (node (ref "Q14") (pin "2") (pinfunction "B_2") (pintype "passive"))
      (node (ref "R17") (pin "1") (pinfunction "1_1") (pintype "passive"))
    )
    (net (code "36") (name "Net-(Q14-C)") (class "Default")
      (node (ref "Q14") (pin "3") (pinfunction "C_3") (pintype "passive"))
      (node (ref "Q4") (pin "2") (pinfunction "B_2") (pintype "passive"))
      (node (ref "R9") (pin "2") (pinfunction "2_2") (pintype "passive"))
    )
    (net (code "37") (name "Net-(Q14-E)") (class "Default")
      (node (ref "Q14") (pin "1") (pinfunction "E_1") (pintype "passive"))
      (node (ref "R23") (pin "2") (pinfunction "2_2") (pintype "passive"))
    )
    (net (code "38") (name "Net-(Q15-B)") (class "Default")
      (node (ref "Q15") (pin "2") (pinfunction "B_2") (pintype "passive"))
      (node (ref "R20") (pin "1") (pinfunction "1_1") (pintype "passive"))
    )
    (net (code "39") (name "Net-(Q15-E)") (class "Default")
      (node (ref "Q15") (pin "1") (pinfunction "E_1") (pintype "passive"))
      (node (ref "R28") (pin "1") (pinfunction "1_1") (pintype "passive"))
    )
    (net (code "40") (name "Net-(Q17-B)") (class "Default")
      (node (ref "Q17") (pin "2") (pinfunction "B_2") (pintype "passive"))
      (node (ref "R19") (pin "1") (pinfunction "1_1") (pintype "passive"))
    )
    (net (code "41") (name "Net-(Q17-C)") (class "Default")
      (node (ref "Q17") (pin "3") (pinfunction "C_3") (pintype "passive"))
      (node (ref "Q5") (pin "2") (pinfunction "B_2") (pintype "passive"))
      (node (ref "R11") (pin "2") (pinfunction "2_2") (pintype "passive"))
    )
    (net (code "42") (name "Net-(Q17-E)") (class "Default")
      (node (ref "Q17") (pin "1") (pinfunction "E_1") (pintype "passive"))
      (node (ref "R27") (pin "2") (pinfunction "2_2") (pintype "passive"))
    )
    (net (code "43") (name "Net-(Q20-B)") (class "Default")
      (node (ref "Q20") (pin "2") (pinfunction "B_2") (pintype "passive"))
      (node (ref "Q26") (pin "3") (pinfunction "C_3") (pintype "passive"))
      (node (ref "R29") (pin "2") (pinfunction "2_2") (pintype "passive"))
    )
    (net (code "44") (name "Net-(Q20-C)") (class "Default")
      (node (ref "Q20") (pin "3") (pinfunction "C_3") (pintype "passive"))
      (node (ref "R34") (pin "1") (pinfunction "1_1") (pintype "passive"))
    )
    (net (code "45") (name "Net-(Q21-B)") (class "Default")
      (node (ref "Q21") (pin "2") (pinfunction "B_2") (pintype "passive"))
      (node (ref "Q22") (pin "3") (pinfunction "C_3") (pintype "passive"))
      (node (ref "R30") (pin "2") (pinfunction "2_2") (pintype "passive"))
    )
    (net (code "46") (name "Net-(Q21-C)") (class "Default")
      (node (ref "Q21") (pin "3") (pinfunction "C_3") (pintype "passive"))
      (node (ref "R33") (pin "2") (pinfunction "2_2") (pintype "passive"))
    )
    (net (code "47") (name "Net-(Q22-E)") (class "Default")
      (node (ref "Q22") (pin "1") (pinfunction "E_1") (pintype "passive"))
      (node (ref "R37") (pin "1") (pinfunction "1_1") (pintype "passive"))
    )
    (net (code "48") (name "Net-(Q23-B)") (class "Default")
      (node (ref "Q23") (pin "2") (pinfunction "B_2") (pintype "passive"))
      (node (ref "Q31") (pin "3") (pinfunction "C_3") (pintype "passive"))
      (node (ref "R31") (pin "2") (pinfunction "2_2") (pintype "passive"))
    )
    (net (code "49") (name "Net-(Q23-C)") (class "Default")
      (node (ref "Q23") (pin "3") (pinfunction "C_3") (pintype "passive"))
      (node (ref "R38") (pin "1") (pinfunction "1_1") (pintype "passive"))
    )
    (net (code "50") (name "Net-(Q24-B)") (class "Default")
      (node (ref "Q24") (pin "2") (pinfunction "B_2") (pintype "passive"))
      (node (ref "Q28") (pin "3") (pinfunction "C_3") (pintype "passive"))
      (node (ref "R32") (pin "2") (pinfunction "2_2") (pintype "passive"))
    )
    (net (code "51") (name "Net-(Q24-C)") (class "Default")
      (node (ref "Q24") (pin "3") (pinfunction "C_3") (pintype "passive"))
      (node (ref "R35") (pin "2") (pinfunction "2_2") (pintype "passive"))
    )
    (net (code "52") (name "Net-(Q25-G)") (class "Default")
      (node (ref "C15") (pin "1") (pinfunction "1_1") (pintype "passive"))
      (node (ref "Q25") (pin "1") (pinfunction "G_1") (pintype "passive"))
      (node (ref "Q33") (pin "3") (pinfunction "C_3") (pintype "passive"))
      (node (ref "R34") (pin "2") (pinfunction "2_2") (pintype "passive"))
    )
    (net (code "53") (name "Net-(Q26-E)") (class "Default")
      (node (ref "Q26") (pin "1") (pinfunction "E_1") (pintype "passive"))
      (node (ref "R36") (pin "2") (pinfunction "2_2") (pintype "passive"))
    )
    (net (code "54") (name "Net-(Q27-G)") (class "Default")
      (node (ref "C16") (pin "1") (pinfunction "1_1") (pintype "passive"))
      (node (ref "Q27") (pin "1") (pinfunction "G_1") (pintype "passive"))
      (node (ref "Q30") (pin "3") (pinfunction "C_3") (pintype "passive"))
      (node (ref "R33") (pin "1") (pinfunction "1_1") (pintype "passive"))
    )
    (net (code "55") (name "Net-(Q28-E)") (class "Default")
      (node (ref "Q28") (pin "1") (pinfunction "E_1") (pintype "passive"))
      (node (ref "R40") (pin "1") (pinfunction "1_1") (pintype "passive"))
    )
    (net (code "56") (name "Net-(Q29-G)") (class "Default")
      (node (ref "C17") (pin "1") (pinfunction "1_1") (pintype "passive"))
      (node (ref "Q29") (pin "1") (pinfunction "G_1") (pintype "passive"))
      (node (ref "Q35") (pin "3") (pinfunction "C_3") (pintype "passive"))
      (node (ref "R38") (pin "2") (pinfunction "2_2") (pintype "passive"))
    )
    (net (code "57") (name "Net-(Q30-B)") (class "Default")
      (node (ref "Q30") (pin "2") (pinfunction "B_2") (pintype "passive"))
      (node (ref "R42") (pin "2") (pinfunction "2_2") (pintype "passive"))
    )
    (net (code "58") (name "Net-(Q31-E)") (class "Default")
      (node (ref "Q31") (pin "1") (pinfunction "E_1") (pintype "passive"))
      (node (ref "R39") (pin "2") (pinfunction "2_2") (pintype "passive"))
    )
    (net (code "59") (name "Net-(Q32-G)") (class "Default")
      (node (ref "C18") (pin "1") (pinfunction "1_1") (pintype "passive"))
      (node (ref "Q32") (pin "1") (pinfunction "G_1") (pintype "passive"))
      (node (ref "Q34") (pin "3") (pinfunction "C_3") (pintype "passive"))
      (node (ref "R35") (pin "1") (pinfunction "1_1") (pintype "passive"))
    )
    (net (code "60") (name "Net-(Q33-B)") (class "Default")
      (node (ref "Q33") (pin "2") (pinfunction "B_2") (pintype "passive"))
      (node (ref "R41") (pin "1") (pinfunction "1_1") (pintype "passive"))
    )
    (net (code "61") (name "Net-(Q34-B)") (class "Default")
      (node (ref "Q34") (pin "2") (pinfunction "B_2") (pintype "passive"))
      (node (ref "R44") (pin "2") (pinfunction "2_2") (pintype "passive"))
    )
    (net (code "62") (name "Net-(Q35-B)") (class "Default")
      (node (ref "Q35") (pin "2") (pinfunction "B_2") (pintype "passive"))
      (node (ref "R43") (pin "1") (pinfunction "1_1") (pintype "passive"))
    )
    (net (code "63") (name "Net-(Q36-B)") (class "Default")
      (node (ref "Q36") (pin "2") (pinfunction "B_2") (pintype "passive"))
      (node (ref "Q37") (pin "3") (pinfunction "C_3") (pintype "passive"))
      (node (ref "Q38") (pin "2") (pinfunction "B_2") (pintype "passive"))
      (node (ref "R45") (pin "1") (pinfunction "1_1") (pintype "passive"))
    )
    (net (code "64") (name "Net-(Q36-E)") (class "Default")
      (node (ref "C19") (pin "2") (pinfunction "2_2") (pintype "passive"))
      (node (ref "Q36") (pin "1") (pinfunction "E_1") (pintype "passive"))
      (node (ref "Q38") (pin "1") (pinfunction "E_1") (pintype "passive"))
    )
    (net (code "65") (name "Net-(Q37-B)") (class "Default")
      (node (ref "Q37") (pin "2") (pinfunction "B_2") (pintype "passive"))
      (node (ref "R46") (pin "1") (pinfunction "1_1") (pintype "passive"))
    )
    (net (code "66") (name "Net-(U4-OUT)") (class "Default")
      (node (ref "R48") (pin "2") (pinfunction "2_2") (pintype "passive"))
      (node (ref "U4") (pin "5") (pinfunction "OUT_5") (pintype "passive"))
    )
    (net (code "67") (name "Net-(U6A-IN+)") (class "Default")
      (node (ref "C27") (pin "2") (pinfunction "2_2") (pintype "passive"))
      (node (ref "R48") (pin "1") (pinfunction "1_1") (pintype "passive"))
      (node (ref "U6") (pin "3") (pinfunction "IN+_3") (pintype "input"))
    )
    (net (code "68") (name "VCC") (class "Default")
      (node (ref "C22") (pin "2") (pinfunction "2_2") (pintype "passive"))
      (node (ref "C23") (pin "1") (pinfunction "1_1") (pintype "passive"))
      (node (ref "C24") (pin "1") (pinfunction "1_1") (pintype "passive"))
      (node (ref "C25") (pin "1") (pinfunction "1_1") (pintype "passive"))
      (node (ref "D14") (pin "1") (pinfunction "A_1") (pintype "passive"))
      (node (ref "R47") (pin "2") (pinfunction "2_2") (pintype "passive"))
      (node (ref "R55") (pin "2") (pinfunction "2_2") (pintype "passive"))
      (node (ref "U4") (pin "1") (pinfunction "RS+_1") (pintype "passive"))
      (node (ref "U4") (pin "2") (pinfunction "VCC_2") (pintype "passive"))
    )
    (net (code "69") (name "VH") (class "Default")
      (node (ref "C20") (pin "2") (pinfunction "2_2") (pintype "passive"))
      (node (ref "D15") (pin "2") (pinfunction "K_2") (pintype "passive"))
      (node (ref "Q10") (pin "1") (pinfunction "E_1") (pintype "passive"))
      (node (ref "Q4") (pin "1") (pinfunction "E_1") (pintype "passive"))
      (node (ref "Q5") (pin "1") (pinfunction "E_1") (pintype "passive"))
      (node (ref "Q6") (pin "1") (pinfunction "E_1") (pintype "passive"))
      (node (ref "R10") (pin "1") (pinfunction "1_1") (pintype "passive"))
      (node (ref "R11") (pin "1") (pinfunction "1_1") (pintype "passive"))
      (node (ref "R12") (pin "1") (pinfunction "1_1") (pintype "passive"))
      (node (ref "R9") (pin "1") (pinfunction "1_1") (pintype "passive"))
    )
    (net (code "70") (name "VP") (class "Default")
      (node (ref "C13") (pin "1") (pinfunction "1_1") (pintype "passive"))
      (node (ref "C14") (pin "1") (pinfunction "1_1") (pintype "passive"))
      (node (ref "Q12") (pin "2") (pinfunction "D_2") (pintype "passive"))
      (node (ref "Q13") (pin "2") (pinfunction "D_2") (pintype "passive"))
      (node (ref "Q7") (pin "2") (pinfunction "D_2") (pintype "passive"))
      (node (ref "Q8") (pin "2") (pinfunction "D_2") (pintype "passive"))
      (node (ref "R47") (pin "1") (pinfunction "1_1") (pintype "passive"))
      (node (ref "R55") (pin "1") (pinfunction "1_1") (pintype "passive"))
      (node (ref "U4") (pin "8") (pinfunction "RS-_8") (pintype "passive"))
    )
    (net (code "71") (name "unconnected-(U4-N.C-Pad3)") (class "Default")
      (node (ref "U4") (pin "3") (pinfunction "N.C_3") (pintype "passive"))
    )
    (net (code "72") (name "unconnected-(U4-N.C-Pad6)") (class "Default")
      (node (ref "U4") (pin "6") (pinfunction "N.C_6") (pintype "passive"))
    )
    (net (code "73") (name "unconnected-(U4-N.C-Pad7)") (class "Default")
      (node (ref "U4") (pin "7") (pinfunction "N.C_7") (pintype "passive"))
    )
  )
)
